# AD_0.net
KiCad netlist of a schematic drawn in Altium Designer
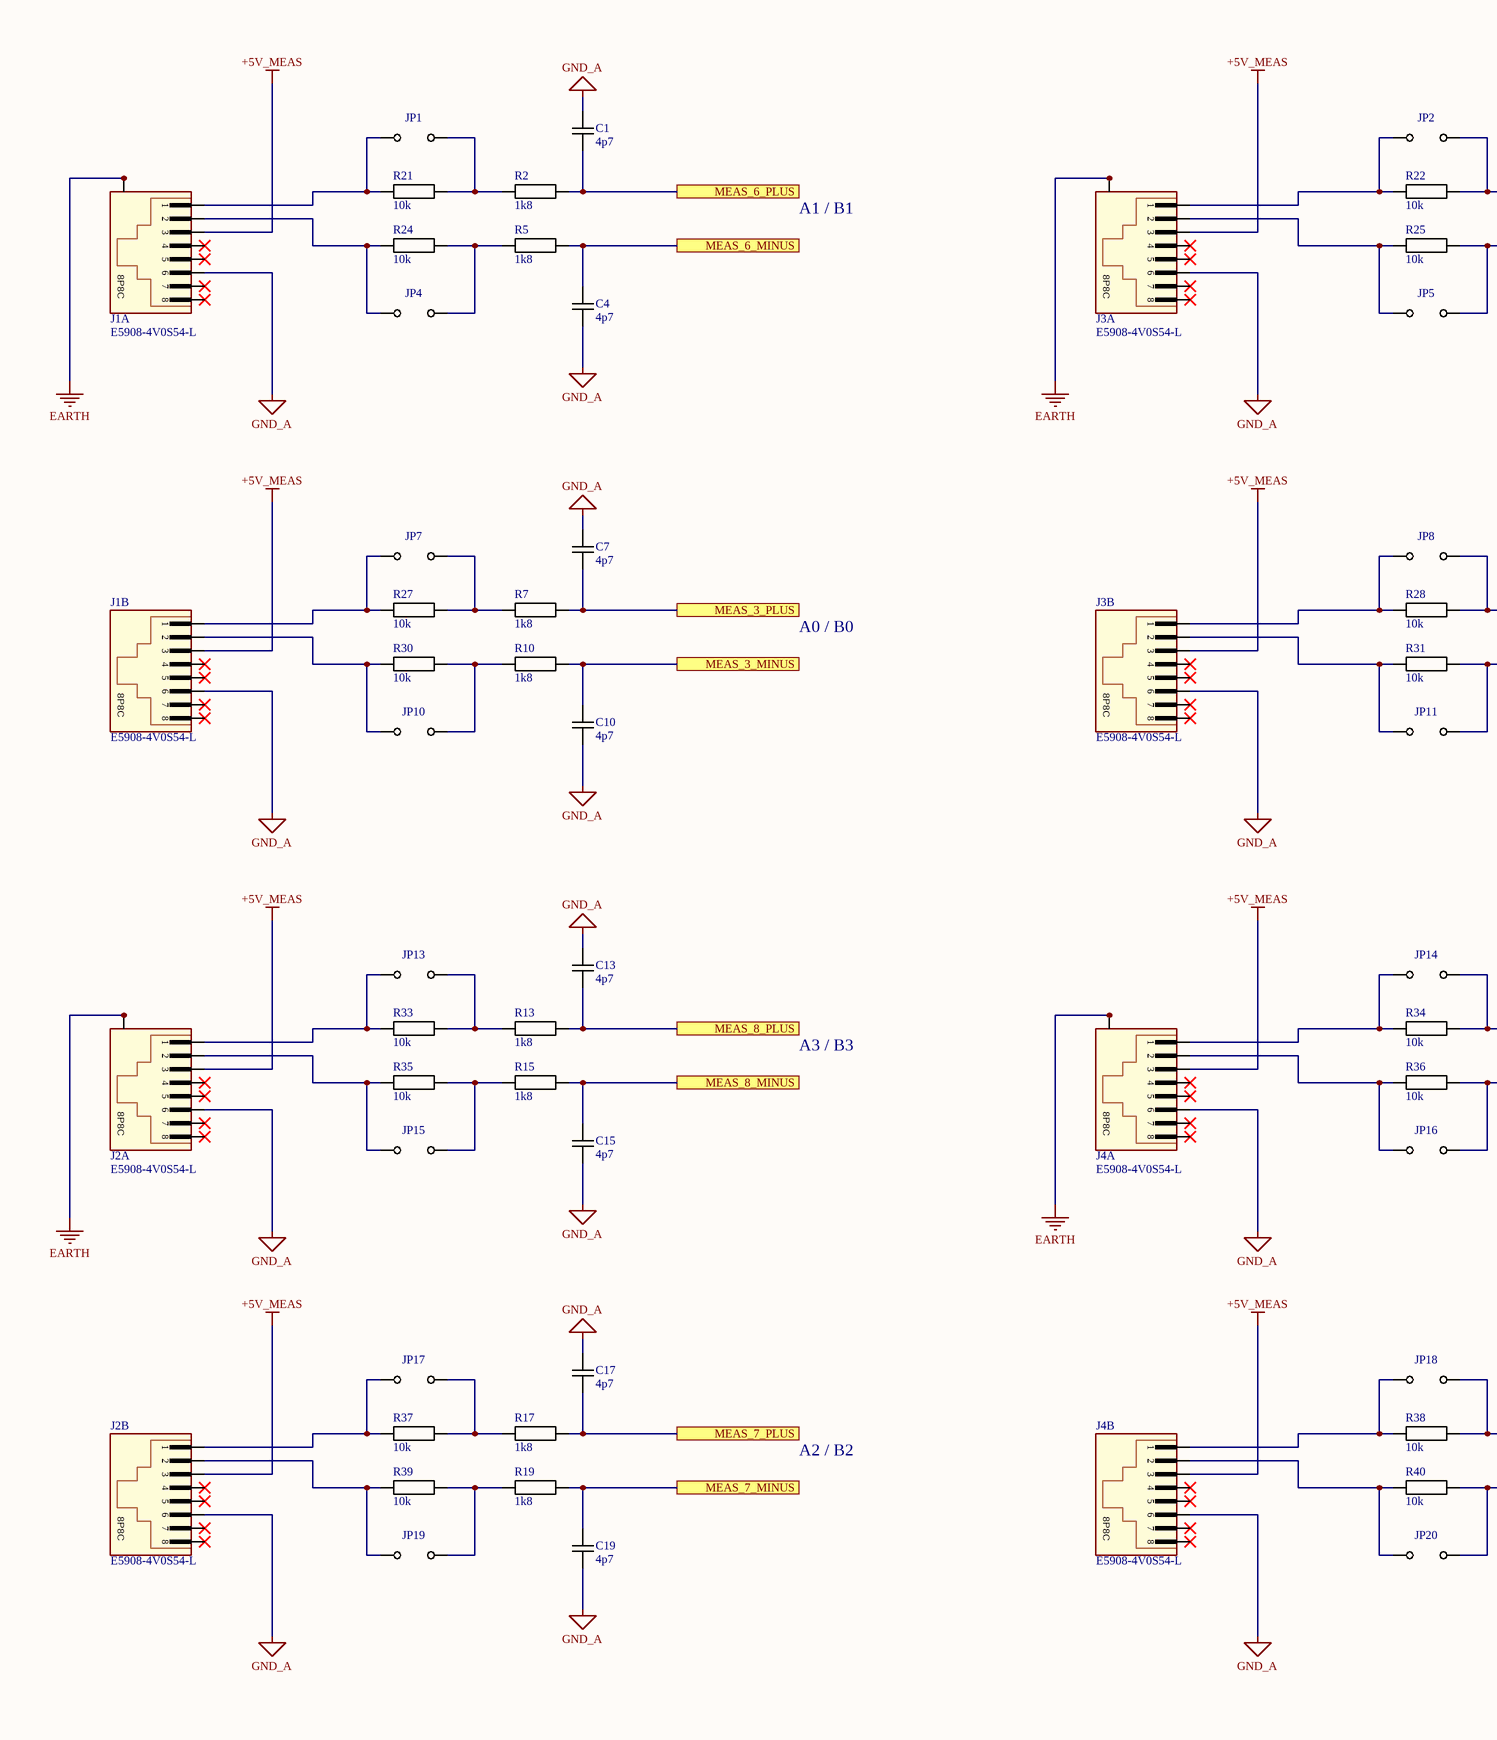
[diagram p0: AD_0.SchDoc, left]
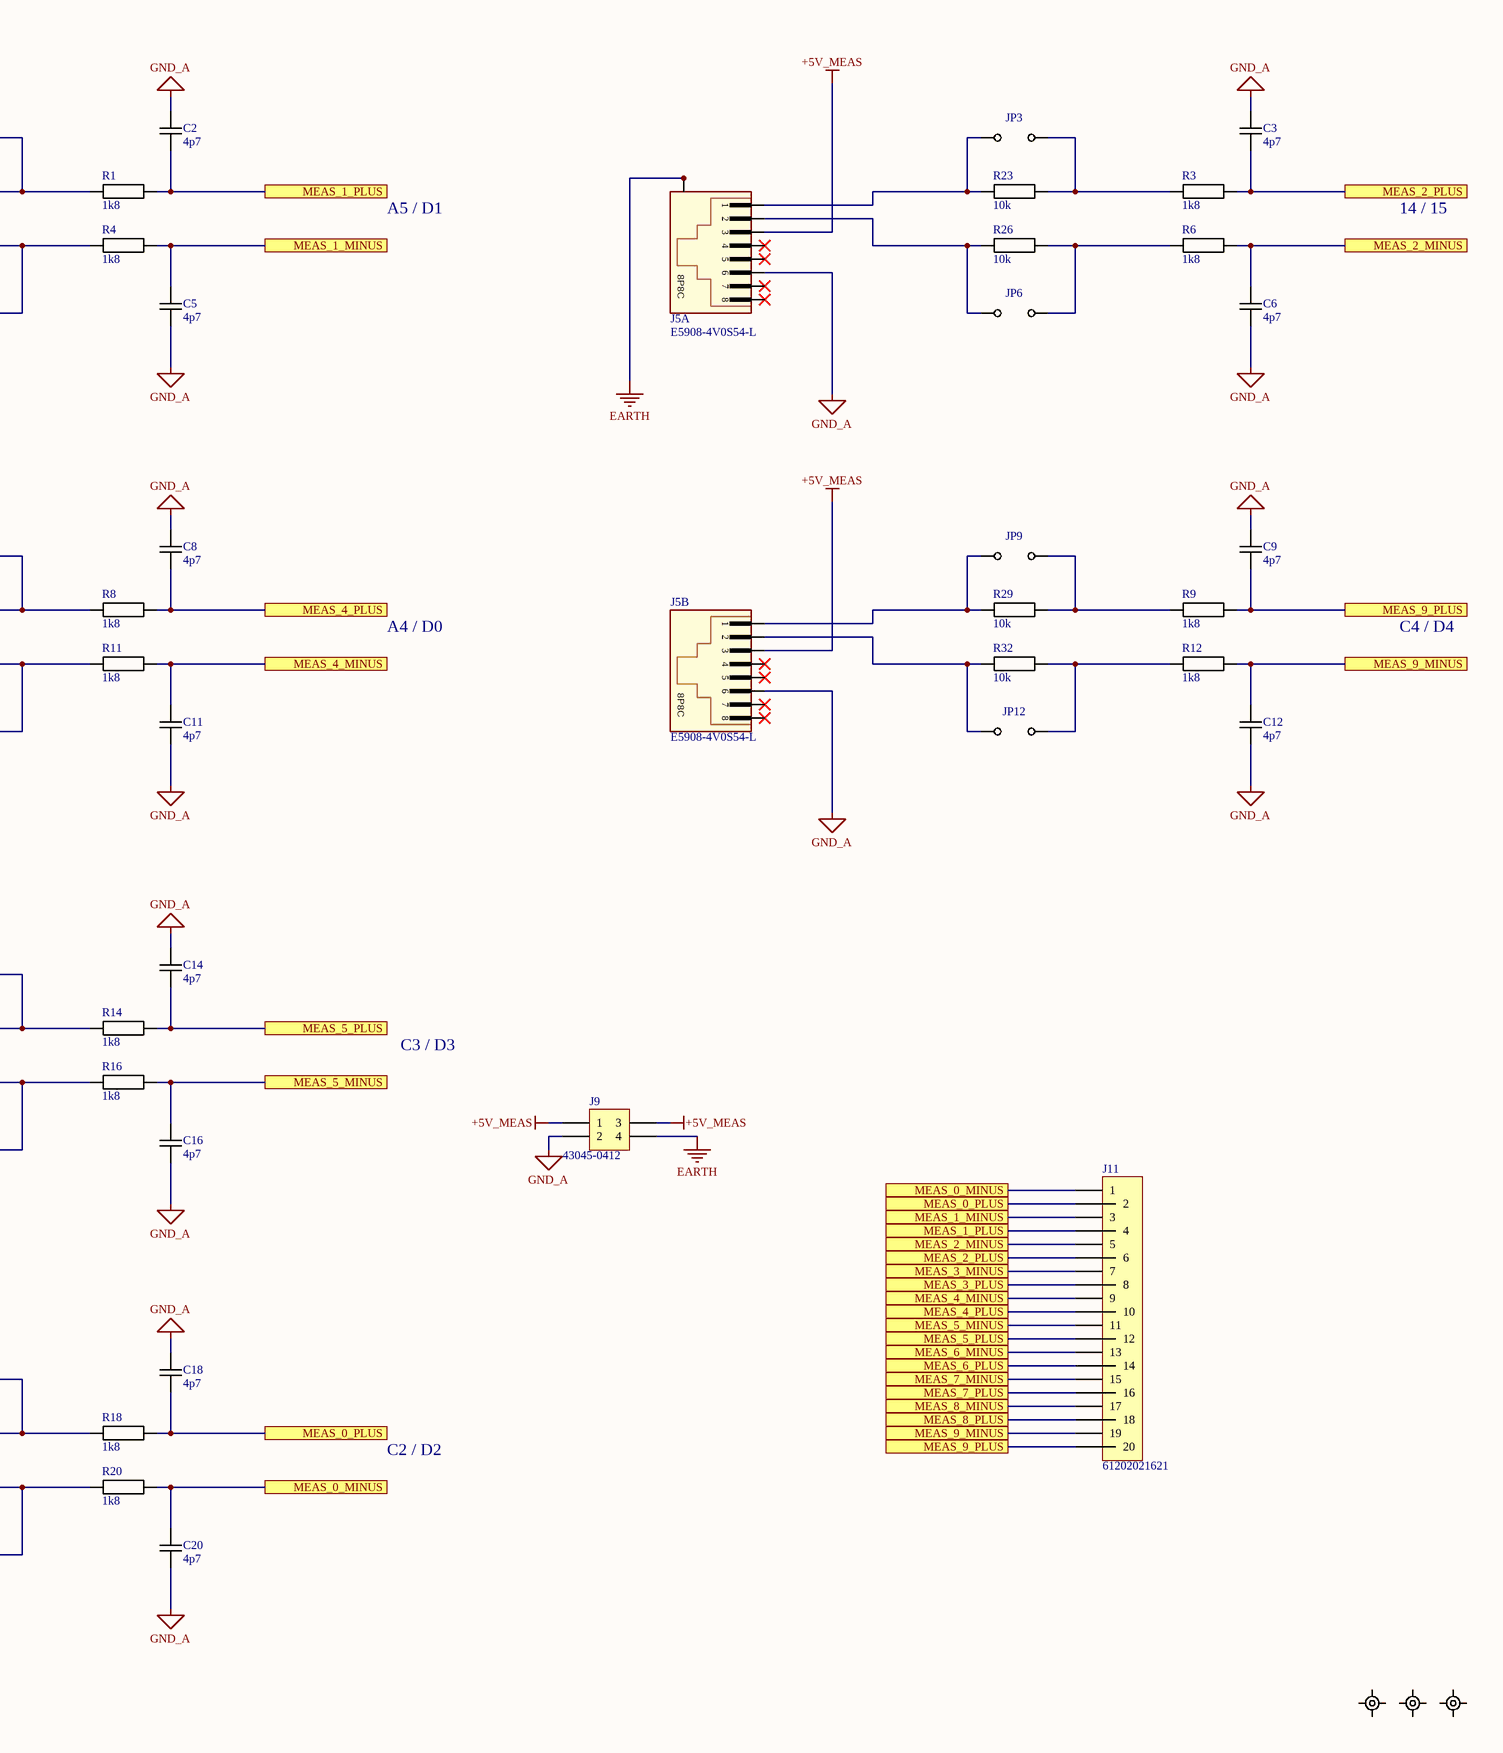
[diagram p1: AD_0.SchDoc, right]

(export (version "E")
  (design (tool "Eeschema 10.0.6"))
  (components
    (comp (ref "C1")
      (value "4p7")
      (footprint "CAPACITOR 2012 REFLOW")
      (description "Capacitor X7R 50V 2012(0805)")
      (libsource (lib "Capacitor") (part "Capacitor"))
    )
    (comp (ref "C2")
      (value "4p7")
      (footprint "CAPACITOR 2012 REFLOW")
      (description "Capacitor X7R 50V 2012(0805)")
      (libsource (lib "Capacitor") (part "Capacitor"))
    )
    (comp (ref "C3")
      (value "4p7")
      (footprint "CAPACITOR 2012 REFLOW")
      (description "Capacitor X7R 50V 2012(0805)")
      (libsource (lib "Capacitor") (part "Capacitor"))
    )
    (comp (ref "C4")
      (value "4p7")
      (footprint "CAPACITOR 2012 REFLOW")
      (description "Capacitor X7R 50V 2012(0805)")
      (libsource (lib "Capacitor") (part "Capacitor"))
    )
    (comp (ref "C5")
      (value "4p7")
      (footprint "CAPACITOR 2012 REFLOW")
      (description "Capacitor X7R 50V 2012(0805)")
      (libsource (lib "Capacitor") (part "Capacitor"))
    )
    (comp (ref "C6")
      (value "4p7")
      (footprint "CAPACITOR 2012 REFLOW")
      (description "Capacitor X7R 50V 2012(0805)")
      (libsource (lib "Capacitor") (part "Capacitor"))
    )
    (comp (ref "C7")
      (value "4p7")
      (footprint "CAPACITOR 2012 REFLOW")
      (description "Capacitor X7R 50V 2012(0805)")
      (libsource (lib "Capacitor") (part "Capacitor"))
    )
    (comp (ref "C8")
      (value "4p7")
      (footprint "CAPACITOR 2012 REFLOW")
      (description "Capacitor X7R 50V 2012(0805)")
      (libsource (lib "Capacitor") (part "Capacitor"))
    )
    (comp (ref "C9")
      (value "4p7")
      (footprint "CAPACITOR 2012 REFLOW")
      (description "Capacitor X7R 50V 2012(0805)")
      (libsource (lib "Capacitor") (part "Capacitor"))
    )
    (comp (ref "C10")
      (value "4p7")
      (footprint "CAPACITOR 2012 REFLOW")
      (description "Capacitor X7R 50V 2012(0805)")
      (libsource (lib "Capacitor") (part "Capacitor"))
    )
    (comp (ref "C11")
      (value "4p7")
      (footprint "CAPACITOR 2012 REFLOW")
      (description "Capacitor X7R 50V 2012(0805)")
      (libsource (lib "Capacitor") (part "Capacitor"))
    )
    (comp (ref "C12")
      (value "4p7")
      (footprint "CAPACITOR 2012 REFLOW")
      (description "Capacitor X7R 50V 2012(0805)")
      (libsource (lib "Capacitor") (part "Capacitor"))
    )
    (comp (ref "C13")
      (value "4p7")
      (footprint "CAPACITOR 2012 REFLOW")
      (description "Capacitor X7R 50V 2012(0805)")
      (libsource (lib "Capacitor") (part "Capacitor"))
    )
    (comp (ref "C14")
      (value "4p7")
      (footprint "CAPACITOR 2012 REFLOW")
      (description "Capacitor X7R 50V 2012(0805)")
      (libsource (lib "Capacitor") (part "Capacitor"))
    )
    (comp (ref "C15")
      (value "4p7")
      (footprint "CAPACITOR 2012 REFLOW")
      (description "Capacitor X7R 50V 2012(0805)")
      (libsource (lib "Capacitor") (part "Capacitor"))
    )
    (comp (ref "C16")
      (value "4p7")
      (footprint "CAPACITOR 2012 REFLOW")
      (description "Capacitor X7R 50V 2012(0805)")
      (libsource (lib "Capacitor") (part "Capacitor"))
    )
    (comp (ref "C17")
      (value "4p7")
      (footprint "CAPACITOR 2012 REFLOW")
      (description "Capacitor X7R 50V 2012(0805)")
      (libsource (lib "Capacitor") (part "Capacitor"))
    )
    (comp (ref "C18")
      (value "4p7")
      (footprint "CAPACITOR 2012 REFLOW")
      (description "Capacitor X7R 50V 2012(0805)")
      (libsource (lib "Capacitor") (part "Capacitor"))
    )
    (comp (ref "C19")
      (value "4p7")
      (footprint "CAPACITOR 2012 REFLOW")
      (description "Capacitor X7R 50V 2012(0805)")
      (libsource (lib "Capacitor") (part "Capacitor"))
    )
    (comp (ref "C20")
      (value "4p7")
      (footprint "CAPACITOR 2012 REFLOW")
      (description "Capacitor X7R 50V 2012(0805)")
      (libsource (lib "Capacitor") (part "Capacitor"))
    )
    (comp (ref "J1")
      (value "E5908-4V0S54-L")
      (footprint "RJ45 8P8C PULSE E5908-4V0S54-L")
      (description "RJ45 2X1 8P8C Ethernet Connectors CONN 30u Au THT")
      (fields (field (name "MANUFACTURER") "Pulse Electronics"))
      (libsource (lib "Connector") (part "RJ45 8P8C PULSE E5908-4V0S54-L"))
    )
    (comp (ref "J2")
      (value "E5908-4V0S54-L")
      (footprint "RJ45 8P8C PULSE E5908-4V0S54-L")
      (description "RJ45 2X1 8P8C Ethernet Connectors CONN 30u Au THT")
      (fields (field (name "MANUFACTURER") "Pulse Electronics"))
      (libsource (lib "Connector") (part "RJ45 8P8C PULSE E5908-4V0S54-L"))
    )
    (comp (ref "J3")
      (value "E5908-4V0S54-L")
      (footprint "RJ45 8P8C PULSE E5908-4V0S54-L")
      (description "RJ45 2X1 8P8C Ethernet Connectors CONN 30u Au THT")
      (fields (field (name "MANUFACTURER") "Pulse Electronics"))
      (libsource (lib "Connector") (part "RJ45 8P8C PULSE E5908-4V0S54-L"))
    )
    (comp (ref "J4")
      (value "E5908-4V0S54-L")
      (footprint "RJ45 8P8C PULSE E5908-4V0S54-L")
      (description "RJ45 2X1 8P8C Ethernet Connectors CONN 30u Au THT")
      (fields (field (name "MANUFACTURER") "Pulse Electronics"))
      (libsource (lib "Connector") (part "RJ45 8P8C PULSE E5908-4V0S54-L"))
    )
    (comp (ref "J5")
      (value "E5908-4V0S54-L")
      (footprint "RJ45 8P8C PULSE E5908-4V0S54-L")
      (description "RJ45 2X1 8P8C Ethernet Connectors CONN 30u Au THT")
      (fields (field (name "MANUFACTURER") "Pulse Electronics"))
      (libsource (lib "Connector") (part "RJ45 8P8C PULSE E5908-4V0S54-L"))
    )
    (comp (ref "J9")
      (value "43045-0412")
      (footprint "MOLEX 43045-0412")
      (description "Micro-Fit 3.0 Vertical Header, 3.00mm Pitch, Dual Row, 4 Circuits")
      (fields (field (name "MANUFACTURER") "Molex"))
      (libsource (lib "Connector") (part "MOLEX 43045-0412"))
    )
    (comp (ref "J11")
      (value "61202021621")
      (footprint "FlatCable2x10 2.54MM Straight TH")
      (description "FlatCable2x10 2.54mm Straight TH")
      (fields (field (name "MANUFACTURER") "Wurth Elektronik"))
      (libsource (lib "Connector") (part "FlatCable2x10"))
    )
    (comp (ref "JP1")
      (value "890-18-036-10-803")
      (footprint "JUMPER2 TH")
      (description "JUMPER 2 POS")
      (fields (field (name "MANUFACTURER") "PRECI-DIP"))
      (libsource (lib "Jumper") (part "JUMPER 2 POS"))
    )
    (comp (ref "JP2")
      (value "890-18-036-10-803")
      (footprint "JUMPER2 TH")
      (description "JUMPER 2 POS")
      (fields (field (name "MANUFACTURER") "PRECI-DIP"))
      (libsource (lib "Jumper") (part "JUMPER 2 POS"))
    )
    (comp (ref "JP3")
      (value "890-18-036-10-803")
      (footprint "JUMPER2 TH")
      (description "JUMPER 2 POS")
      (fields (field (name "MANUFACTURER") "PRECI-DIP"))
      (libsource (lib "Jumper") (part "JUMPER 2 POS"))
    )
    (comp (ref "JP4")
      (value "890-18-036-10-803")
      (footprint "JUMPER2 TH")
      (description "JUMPER 2 POS")
      (fields (field (name "MANUFACTURER") "PRECI-DIP"))
      (libsource (lib "Jumper") (part "JUMPER 2 POS"))
    )
    (comp (ref "JP5")
      (value "890-18-036-10-803")
      (footprint "JUMPER2 TH")
      (description "JUMPER 2 POS")
      (fields (field (name "MANUFACTURER") "PRECI-DIP"))
      (libsource (lib "Jumper") (part "JUMPER 2 POS"))
    )
    (comp (ref "JP6")
      (value "890-18-036-10-803")
      (footprint "JUMPER2 TH")
      (description "JUMPER 2 POS")
      (fields (field (name "MANUFACTURER") "PRECI-DIP"))
      (libsource (lib "Jumper") (part "JUMPER 2 POS"))
    )
    (comp (ref "JP7")
      (value "890-18-036-10-803")
      (footprint "JUMPER2 TH")
      (description "JUMPER 2 POS")
      (fields (field (name "MANUFACTURER") "PRECI-DIP"))
      (libsource (lib "Jumper") (part "JUMPER 2 POS"))
    )
    (comp (ref "JP8")
      (value "890-18-036-10-803")
      (footprint "JUMPER2 TH")
      (description "JUMPER 2 POS")
      (fields (field (name "MANUFACTURER") "PRECI-DIP"))
      (libsource (lib "Jumper") (part "JUMPER 2 POS"))
    )
    (comp (ref "JP9")
      (value "890-18-036-10-803")
      (footprint "JUMPER2 TH")
      (description "JUMPER 2 POS")
      (fields (field (name "MANUFACTURER") "PRECI-DIP"))
      (libsource (lib "Jumper") (part "JUMPER 2 POS"))
    )
    (comp (ref "JP10")
      (value "890-18-036-10-803")
      (footprint "JUMPER2 TH")
      (description "JUMPER 2 POS")
      (fields (field (name "MANUFACTURER") "PRECI-DIP"))
      (libsource (lib "Jumper") (part "JUMPER 2 POS"))
    )
    (comp (ref "JP11")
      (value "890-18-036-10-803")
      (footprint "JUMPER2 TH")
      (description "JUMPER 2 POS")
      (fields (field (name "MANUFACTURER") "PRECI-DIP"))
      (libsource (lib "Jumper") (part "JUMPER 2 POS"))
    )
    (comp (ref "JP12")
      (value "890-18-036-10-803")
      (footprint "JUMPER2 TH")
      (description "JUMPER 2 POS")
      (fields (field (name "MANUFACTURER") "PRECI-DIP"))
      (libsource (lib "Jumper") (part "JUMPER 2 POS"))
    )
    (comp (ref "JP13")
      (value "890-18-036-10-803")
      (footprint "JUMPER2 TH")
      (description "JUMPER 2 POS")
      (fields (field (name "MANUFACTURER") "PRECI-DIP"))
      (libsource (lib "Jumper") (part "JUMPER 2 POS"))
    )
    (comp (ref "JP14")
      (value "890-18-036-10-803")
      (footprint "JUMPER2 TH")
      (description "JUMPER 2 POS")
      (fields (field (name "MANUFACTURER") "PRECI-DIP"))
      (libsource (lib "Jumper") (part "JUMPER 2 POS"))
    )
    (comp (ref "JP15")
      (value "890-18-036-10-803")
      (footprint "JUMPER2 TH")
      (description "JUMPER 2 POS")
      (fields (field (name "MANUFACTURER") "PRECI-DIP"))
      (libsource (lib "Jumper") (part "JUMPER 2 POS"))
    )
    (comp (ref "JP16")
      (value "890-18-036-10-803")
      (footprint "JUMPER2 TH")
      (description "JUMPER 2 POS")
      (fields (field (name "MANUFACTURER") "PRECI-DIP"))
      (libsource (lib "Jumper") (part "JUMPER 2 POS"))
    )
    (comp (ref "JP17")
      (value "890-18-036-10-803")
      (footprint "JUMPER2 TH")
      (description "JUMPER 2 POS")
      (fields (field (name "MANUFACTURER") "PRECI-DIP"))
      (libsource (lib "Jumper") (part "JUMPER 2 POS"))
    )
    (comp (ref "JP18")
      (value "890-18-036-10-803")
      (footprint "JUMPER2 TH")
      (description "JUMPER 2 POS")
      (fields (field (name "MANUFACTURER") "PRECI-DIP"))
      (libsource (lib "Jumper") (part "JUMPER 2 POS"))
    )
    (comp (ref "JP19")
      (value "890-18-036-10-803")
      (footprint "JUMPER2 TH")
      (description "JUMPER 2 POS")
      (fields (field (name "MANUFACTURER") "PRECI-DIP"))
      (libsource (lib "Jumper") (part "JUMPER 2 POS"))
    )
    (comp (ref "JP20")
      (value "890-18-036-10-803")
      (footprint "JUMPER2 TH")
      (description "JUMPER 2 POS")
      (fields (field (name "MANUFACTURER") "PRECI-DIP"))
      (libsource (lib "Jumper") (part "JUMPER 2 POS"))
    )
    (comp (ref "R1")
      (value "1k8")
      (footprint "RESISTOR 2012 REFLOW")
      (description "Resistor 1% 50V 125mW 2012(0805)")
      (libsource (lib "Resistor") (part "Resistor"))
    )
    (comp (ref "R2")
      (value "1k8")
      (footprint "RESISTOR 2012 REFLOW")
      (description "Resistor 1% 50V 125mW 2012(0805)")
      (libsource (lib "Resistor") (part "Resistor"))
    )
    (comp (ref "R3")
      (value "1k8")
      (footprint "RESISTOR 2012 REFLOW")
      (description "Resistor 1% 50V 125mW 2012(0805)")
      (libsource (lib "Resistor") (part "Resistor"))
    )
    (comp (ref "R4")
      (value "1k8")
      (footprint "RESISTOR 2012 REFLOW")
      (description "Resistor 1% 50V 125mW 2012(0805)")
      (libsource (lib "Resistor") (part "Resistor"))
    )
    (comp (ref "R5")
      (value "1k8")
      (footprint "RESISTOR 2012 REFLOW")
      (description "Resistor 1% 50V 125mW 2012(0805)")
      (libsource (lib "Resistor") (part "Resistor"))
    )
    (comp (ref "R6")
      (value "1k8")
      (footprint "RESISTOR 2012 REFLOW")
      (description "Resistor 1% 50V 125mW 2012(0805)")
      (libsource (lib "Resistor") (part "Resistor"))
    )
    (comp (ref "R7")
      (value "1k8")
      (footprint "RESISTOR 2012 REFLOW")
      (description "Resistor 1% 50V 125mW 2012(0805)")
      (libsource (lib "Resistor") (part "Resistor"))
    )
    (comp (ref "R8")
      (value "1k8")
      (footprint "RESISTOR 2012 REFLOW")
      (description "Resistor 1% 50V 125mW 2012(0805)")
      (libsource (lib "Resistor") (part "Resistor"))
    )
    (comp (ref "R9")
      (value "1k8")
      (footprint "RESISTOR 2012 REFLOW")
      (description "Resistor 1% 50V 125mW 2012(0805)")
      (libsource (lib "Resistor") (part "Resistor"))
    )
    (comp (ref "R10")
      (value "1k8")
      (footprint "RESISTOR 2012 REFLOW")
      (description "Resistor 1% 50V 125mW 2012(0805)")
      (libsource (lib "Resistor") (part "Resistor"))
    )
    (comp (ref "R11")
      (value "1k8")
      (footprint "RESISTOR 2012 REFLOW")
      (description "Resistor 1% 50V 125mW 2012(0805)")
      (libsource (lib "Resistor") (part "Resistor"))
    )
    (comp (ref "R12")
      (value "1k8")
      (footprint "RESISTOR 2012 REFLOW")
      (description "Resistor 1% 50V 125mW 2012(0805)")
      (libsource (lib "Resistor") (part "Resistor"))
    )
    (comp (ref "R13")
      (value "1k8")
      (footprint "RESISTOR 2012 REFLOW")
      (description "Resistor 1% 50V 125mW 2012(0805)")
      (libsource (lib "Resistor") (part "Resistor"))
    )
    (comp (ref "R14")
      (value "1k8")
      (footprint "RESISTOR 2012 REFLOW")
      (description "Resistor 1% 50V 125mW 2012(0805)")
      (libsource (lib "Resistor") (part "Resistor"))
    )
    (comp (ref "R15")
      (value "1k8")
      (footprint "RESISTOR 2012 REFLOW")
      (description "Resistor 1% 50V 125mW 2012(0805)")
      (libsource (lib "Resistor") (part "Resistor"))
    )
    (comp (ref "R16")
      (value "1k8")
      (footprint "RESISTOR 2012 REFLOW")
      (description "Resistor 1% 50V 125mW 2012(0805)")
      (libsource (lib "Resistor") (part "Resistor"))
    )
    (comp (ref "R17")
      (value "1k8")
      (footprint "RESISTOR 2012 REFLOW")
      (description "Resistor 1% 50V 125mW 2012(0805)")
      (libsource (lib "Resistor") (part "Resistor"))
    )
    (comp (ref "R18")
      (value "1k8")
      (footprint "RESISTOR 2012 REFLOW")
      (description "Resistor 1% 50V 125mW 2012(0805)")
      (libsource (lib "Resistor") (part "Resistor"))
    )
    (comp (ref "R19")
      (value "1k8")
      (footprint "RESISTOR 2012 REFLOW")
      (description "Resistor 1% 50V 125mW 2012(0805)")
      (libsource (lib "Resistor") (part "Resistor"))
    )
    (comp (ref "R20")
      (value "1k8")
      (footprint "RESISTOR 2012 REFLOW")
      (description "Resistor 1% 50V 125mW 2012(0805)")
      (libsource (lib "Resistor") (part "Resistor"))
    )
    (comp (ref "R21")
      (value "10k")
      (footprint "RESISTOR 2012 REFLOW")
      (description "Resistor 1% 50V 125mW 2012(0805)")
      (libsource (lib "Resistor") (part "Resistor"))
    )
    (comp (ref "R22")
      (value "10k")
      (footprint "RESISTOR 2012 REFLOW")
      (description "Resistor 1% 50V 125mW 2012(0805)")
      (libsource (lib "Resistor") (part "Resistor"))
    )
    (comp (ref "R23")
      (value "10k")
      (footprint "RESISTOR 2012 REFLOW")
      (description "Resistor 1% 50V 125mW 2012(0805)")
      (libsource (lib "Resistor") (part "Resistor"))
    )
    (comp (ref "R24")
      (value "10k")
      (footprint "RESISTOR 2012 REFLOW")
      (description "Resistor 1% 50V 125mW 2012(0805)")
      (libsource (lib "Resistor") (part "Resistor"))
    )
    (comp (ref "R25")
      (value "10k")
      (footprint "RESISTOR 2012 REFLOW")
      (description "Resistor 1% 50V 125mW 2012(0805)")
      (libsource (lib "Resistor") (part "Resistor"))
    )
    (comp (ref "R26")
      (value "10k")
      (footprint "RESISTOR 2012 REFLOW")
      (description "Resistor 1% 50V 125mW 2012(0805)")
      (libsource (lib "Resistor") (part "Resistor"))
    )
    (comp (ref "R27")
      (value "10k")
      (footprint "RESISTOR 2012 REFLOW")
      (description "Resistor 1% 50V 125mW 2012(0805)")
      (libsource (lib "Resistor") (part "Resistor"))
    )
    (comp (ref "R28")
      (value "10k")
      (footprint "RESISTOR 2012 REFLOW")
      (description "Resistor 1% 50V 125mW 2012(0805)")
      (libsource (lib "Resistor") (part "Resistor"))
    )
    (comp (ref "R29")
      (value "10k")
      (footprint "RESISTOR 2012 REFLOW")
      (description "Resistor 1% 50V 125mW 2012(0805)")
      (libsource (lib "Resistor") (part "Resistor"))
    )
    (comp (ref "R30")
      (value "10k")
      (footprint "RESISTOR 2012 REFLOW")
      (description "Resistor 1% 50V 125mW 2012(0805)")
      (libsource (lib "Resistor") (part "Resistor"))
    )
    (comp (ref "R31")
      (value "10k")
      (footprint "RESISTOR 2012 REFLOW")
      (description "Resistor 1% 50V 125mW 2012(0805)")
      (libsource (lib "Resistor") (part "Resistor"))
    )
    (comp (ref "R32")
      (value "10k")
      (footprint "RESISTOR 2012 REFLOW")
      (description "Resistor 1% 50V 125mW 2012(0805)")
      (libsource (lib "Resistor") (part "Resistor"))
    )
    (comp (ref "R33")
      (value "10k")
      (footprint "RESISTOR 2012 REFLOW")
      (description "Resistor 1% 50V 125mW 2012(0805)")
      (libsource (lib "Resistor") (part "Resistor"))
    )
    (comp (ref "R34")
      (value "10k")
      (footprint "RESISTOR 2012 REFLOW")
      (description "Resistor 1% 50V 125mW 2012(0805)")
      (libsource (lib "Resistor") (part "Resistor"))
    )
    (comp (ref "R35")
      (value "10k")
      (footprint "RESISTOR 2012 REFLOW")
      (description "Resistor 1% 50V 125mW 2012(0805)")
      (libsource (lib "Resistor") (part "Resistor"))
    )
    (comp (ref "R36")
      (value "10k")
      (footprint "RESISTOR 2012 REFLOW")
      (description "Resistor 1% 50V 125mW 2012(0805)")
      (libsource (lib "Resistor") (part "Resistor"))
    )
    (comp (ref "R37")
      (value "10k")
      (footprint "RESISTOR 2012 REFLOW")
      (description "Resistor 1% 50V 125mW 2012(0805)")
      (libsource (lib "Resistor") (part "Resistor"))
    )
    (comp (ref "R38")
      (value "10k")
      (footprint "RESISTOR 2012 REFLOW")
      (description "Resistor 1% 50V 125mW 2012(0805)")
      (libsource (lib "Resistor") (part "Resistor"))
    )
    (comp (ref "R39")
      (value "10k")
      (footprint "RESISTOR 2012 REFLOW")
      (description "Resistor 1% 50V 125mW 2012(0805)")
      (libsource (lib "Resistor") (part "Resistor"))
    )
    (comp (ref "R40")
      (value "10k")
      (footprint "RESISTOR 2012 REFLOW")
      (description "Resistor 1% 50V 125mW 2012(0805)")
      (libsource (lib "Resistor") (part "Resistor"))
    )
    (comp (ref "Z1")
      (value "1 - 3")
      (footprint "FIDUCIAL")
      (description "FIDUCIAL Din 1mm Dout 3mm")
      (libsource (lib "Mechanic") (part "FIDUCIAL"))
    )
    (comp (ref "Z2")
      (value "1 - 3")
      (footprint "FIDUCIAL")
      (description "FIDUCIAL Din 1mm Dout 3mm")
      (libsource (lib "Mechanic") (part "FIDUCIAL"))
    )
    (comp (ref "Z3")
      (value "1 - 3")
      (footprint "FIDUCIAL")
      (description "FIDUCIAL Din 1mm Dout 3mm")
      (libsource (lib "Mechanic") (part "FIDUCIAL"))
    )
  )
  (nets
    (net (code "1") (name "+5V_MEAS") (class "Default")
      (node (ref "J1") (pin "3A") (pinfunction "3A_3A") (pintype "passive"))
      (node (ref "J1") (pin "3B") (pinfunction "3B_3B") (pintype "passive"))
      (node (ref "J2") (pin "3A") (pinfunction "3A_3A") (pintype "passive"))
      (node (ref "J2") (pin "3B") (pinfunction "3B_3B") (pintype "passive"))
      (node (ref "J3") (pin "3A") (pinfunction "3A_3A") (pintype "passive"))
      (node (ref "J3") (pin "3B") (pinfunction "3B_3B") (pintype "passive"))
      (node (ref "J4") (pin "3A") (pinfunction "3A_3A") (pintype "passive"))
      (node (ref "J4") (pin "3B") (pinfunction "3B_3B") (pintype "passive"))
      (node (ref "J5") (pin "3A") (pinfunction "3A_3A") (pintype "passive"))
      (node (ref "J5") (pin "3B") (pinfunction "3B_3B") (pintype "passive"))
      (node (ref "J9") (pin "1") (pinfunction "1_1") (pintype "passive"))
      (node (ref "J9") (pin "3") (pinfunction "3_3") (pintype "passive"))
    )
    (net (code "2") (name "/MEAS_0_MINUS") (class "Default")
      (node (ref "C20") (pin "2") (pinfunction "2_2") (pintype "passive"))
      (node (ref "J11") (pin "1") (pinfunction "1_1") (pintype "passive"))
      (node (ref "R20") (pin "2") (pinfunction "2_2") (pintype "passive"))
    )
    (net (code "3") (name "/MEAS_0_PLUS") (class "Default")
      (node (ref "C18") (pin "1") (pinfunction "1_1") (pintype "passive"))
      (node (ref "J11") (pin "2") (pinfunction "2_2") (pintype "passive"))
      (node (ref "R18") (pin "2") (pinfunction "2_2") (pintype "passive"))
    )
    (net (code "4") (name "/MEAS_1_MINUS") (class "Default")
      (node (ref "C5") (pin "2") (pinfunction "2_2") (pintype "passive"))
      (node (ref "J11") (pin "3") (pinfunction "3_3") (pintype "passive"))
      (node (ref "R4") (pin "2") (pinfunction "2_2") (pintype "passive"))
    )
    (net (code "5") (name "/MEAS_1_PLUS") (class "Default")
      (node (ref "C2") (pin "1") (pinfunction "1_1") (pintype "passive"))
      (node (ref "J11") (pin "4") (pinfunction "4_4") (pintype "passive"))
      (node (ref "R1") (pin "2") (pinfunction "2_2") (pintype "passive"))
    )
    (net (code "6") (name "/MEAS_2_MINUS") (class "Default")
      (node (ref "C6") (pin "2") (pinfunction "2_2") (pintype "passive"))
      (node (ref "J11") (pin "5") (pinfunction "5_5") (pintype "passive"))
      (node (ref "R6") (pin "2") (pinfunction "2_2") (pintype "passive"))
    )
    (net (code "7") (name "/MEAS_2_PLUS") (class "Default")
      (node (ref "C3") (pin "1") (pinfunction "1_1") (pintype "passive"))
      (node (ref "J11") (pin "6") (pinfunction "6_6") (pintype "passive"))
      (node (ref "R3") (pin "2") (pinfunction "2_2") (pintype "passive"))
    )
    (net (code "8") (name "/MEAS_3_MINUS") (class "Default")
      (node (ref "C10") (pin "2") (pinfunction "2_2") (pintype "passive"))
      (node (ref "J11") (pin "7") (pinfunction "7_7") (pintype "passive"))
      (node (ref "R10") (pin "2") (pinfunction "2_2") (pintype "passive"))
    )
    (net (code "9") (name "/MEAS_3_PLUS") (class "Default")
      (node (ref "C7") (pin "1") (pinfunction "1_1") (pintype "passive"))
      (node (ref "J11") (pin "8") (pinfunction "8_8") (pintype "passive"))
      (node (ref "R7") (pin "2") (pinfunction "2_2") (pintype "passive"))
    )
    (net (code "10") (name "/MEAS_4_MINUS") (class "Default")
      (node (ref "C11") (pin "2") (pinfunction "2_2") (pintype "passive"))
      (node (ref "J11") (pin "9") (pinfunction "9_9") (pintype "passive"))
      (node (ref "R11") (pin "2") (pinfunction "2_2") (pintype "passive"))
    )
    (net (code "11") (name "/MEAS_4_PLUS") (class "Default")
      (node (ref "C8") (pin "1") (pinfunction "1_1") (pintype "passive"))
      (node (ref "J11") (pin "10") (pinfunction "10_10") (pintype "passive"))
      (node (ref "R8") (pin "2") (pinfunction "2_2") (pintype "passive"))
    )
    (net (code "12") (name "/MEAS_5_MINUS") (class "Default")
      (node (ref "C16") (pin "2") (pinfunction "2_2") (pintype "passive"))
      (node (ref "J11") (pin "11") (pinfunction "11_11") (pintype "passive"))
      (node (ref "R16") (pin "2") (pinfunction "2_2") (pintype "passive"))
    )
    (net (code "13") (name "/MEAS_5_PLUS") (class "Default")
      (node (ref "C14") (pin "1") (pinfunction "1_1") (pintype "passive"))
      (node (ref "J11") (pin "12") (pinfunction "12_12") (pintype "passive"))
      (node (ref "R14") (pin "2") (pinfunction "2_2") (pintype "passive"))
    )
    (net (code "14") (name "/MEAS_6_MINUS") (class "Default")
      (node (ref "C4") (pin "2") (pinfunction "2_2") (pintype "passive"))
      (node (ref "J11") (pin "13") (pinfunction "13_13") (pintype "passive"))
      (node (ref "R5") (pin "2") (pinfunction "2_2") (pintype "passive"))
    )
    (net (code "15") (name "/MEAS_6_PLUS") (class "Default")
      (node (ref "C1") (pin "1") (pinfunction "1_1") (pintype "passive"))
      (node (ref "J11") (pin "14") (pinfunction "14_14") (pintype "passive"))
      (node (ref "R2") (pin "2") (pinfunction "2_2") (pintype "passive"))
    )
    (net (code "16") (name "/MEAS_7_MINUS") (class "Default")
      (node (ref "C19") (pin "2") (pinfunction "2_2") (pintype "passive"))
      (node (ref "J11") (pin "15") (pinfunction "15_15") (pintype "passive"))
      (node (ref "R19") (pin "2") (pinfunction "2_2") (pintype "passive"))
    )
    (net (code "17") (name "/MEAS_7_PLUS") (class "Default")
      (node (ref "C17") (pin "1") (pinfunction "1_1") (pintype "passive"))
      (node (ref "J11") (pin "16") (pinfunction "16_16") (pintype "passive"))
      (node (ref "R17") (pin "2") (pinfunction "2_2") (pintype "passive"))
    )
    (net (code "18") (name "/MEAS_8_MINUS") (class "Default")
      (node (ref "C15") (pin "2") (pinfunction "2_2") (pintype "passive"))
      (node (ref "J11") (pin "17") (pinfunction "17_17") (pintype "passive"))
      (node (ref "R15") (pin "2") (pinfunction "2_2") (pintype "passive"))
    )
    (net (code "19") (name "/MEAS_8_PLUS") (class "Default")
      (node (ref "C13") (pin "1") (pinfunction "1_1") (pintype "passive"))
      (node (ref "J11") (pin "18") (pinfunction "18_18") (pintype "passive"))
      (node (ref "R13") (pin "2") (pinfunction "2_2") (pintype "passive"))
    )
    (net (code "20") (name "/MEAS_9_MINUS") (class "Default")
      (node (ref "C12") (pin "2") (pinfunction "2_2") (pintype "passive"))
      (node (ref "J11") (pin "19") (pinfunction "19_19") (pintype "passive"))
      (node (ref "R12") (pin "2") (pinfunction "2_2") (pintype "passive"))
    )
    (net (code "21") (name "/MEAS_9_PLUS") (class "Default")
      (node (ref "C9") (pin "1") (pinfunction "1_1") (pintype "passive"))
      (node (ref "J11") (pin "20") (pinfunction "20_20") (pintype "passive"))
      (node (ref "R9") (pin "2") (pinfunction "2_2") (pintype "passive"))
    )
    (net (code "22") (name "EARTH") (class "Default")
      (node (ref "J1") (pin "10") (pinfunction "10_10") (pintype "passive"))
      (node (ref "J1") (pin "11") (pinfunction "11_11") (pintype "passive"))
      (node (ref "J1") (pin "12") (pinfunction "SHIELD_12") (pintype "passive"))
      (node (ref "J1") (pin "9") (pinfunction "9_9") (pintype "passive"))
      (node (ref "J2") (pin "10") (pinfunction "10_10") (pintype "passive"))
      (node (ref "J2") (pin "11") (pinfunction "11_11") (pintype "passive"))
      (node (ref "J2") (pin "12") (pinfunction "SHIELD_12") (pintype "passive"))
      (node (ref "J2") (pin "9") (pinfunction "9_9") (pintype "passive"))
      (node (ref "J3") (pin "10") (pinfunction "10_10") (pintype "passive"))
      (node (ref "J3") (pin "11") (pinfunction "11_11") (pintype "passive"))
      (node (ref "J3") (pin "12") (pinfunction "SHIELD_12") (pintype "passive"))
      (node (ref "J3") (pin "9") (pinfunction "9_9") (pintype "passive"))
      (node (ref "J4") (pin "10") (pinfunction "10_10") (pintype "passive"))
      (node (ref "J4") (pin "11") (pinfunction "11_11") (pintype "passive"))
      (node (ref "J4") (pin "12") (pinfunction "SHIELD_12") (pintype "passive"))
      (node (ref "J4") (pin "9") (pinfunction "9_9") (pintype "passive"))
      (node (ref "J5") (pin "10") (pinfunction "10_10") (pintype "passive"))
      (node (ref "J5") (pin "11") (pinfunction "11_11") (pintype "passive"))
      (node (ref "J5") (pin "12") (pinfunction "SHIELD_12") (pintype "passive"))
      (node (ref "J5") (pin "9") (pinfunction "9_9") (pintype "passive"))
      (node (ref "J9") (pin "4") (pinfunction "4_4") (pintype "passive"))
    )
    (net (code "23") (name "GND_A") (class "Default")
      (node (ref "C1") (pin "2") (pinfunction "2_2") (pintype "passive"))
      (node (ref "C10") (pin "1") (pinfunction "1_1") (pintype "passive"))
      (node (ref "C11") (pin "1") (pinfunction "1_1") (pintype "passive"))
      (node (ref "C12") (pin "1") (pinfunction "1_1") (pintype "passive"))
      (node (ref "C13") (pin "2") (pinfunction "2_2") (pintype "passive"))
      (node (ref "C14") (pin "2") (pinfunction "2_2") (pintype "passive"))
      (node (ref "C15") (pin "1") (pinfunction "1_1") (pintype "passive"))
      (node (ref "C16") (pin "1") (pinfunction "1_1") (pintype "passive"))
      (node (ref "C17") (pin "2") (pinfunction "2_2") (pintype "passive"))
      (node (ref "C18") (pin "2") (pinfunction "2_2") (pintype "passive"))
      (node (ref "C19") (pin "1") (pinfunction "1_1") (pintype "passive"))
      (node (ref "C2") (pin "2") (pinfunction "2_2") (pintype "passive"))
      (node (ref "C20") (pin "1") (pinfunction "1_1") (pintype "passive"))
      (node (ref "C3") (pin "2") (pinfunction "2_2") (pintype "passive"))
      (node (ref "C4") (pin "1") (pinfunction "1_1") (pintype "passive"))
      (node (ref "C5") (pin "1") (pinfunction "1_1") (pintype "passive"))
      (node (ref "C6") (pin "1") (pinfunction "1_1") (pintype "passive"))
      (node (ref "C7") (pin "2") (pinfunction "2_2") (pintype "passive"))
      (node (ref "C8") (pin "2") (pinfunction "2_2") (pintype "passive"))
      (node (ref "C9") (pin "2") (pinfunction "2_2") (pintype "passive"))
      (node (ref "J1") (pin "6A") (pinfunction "6A_6A") (pintype "passive"))
      (node (ref "J1") (pin "6B") (pinfunction "6B_6B") (pintype "passive"))
      (node (ref "J2") (pin "6A") (pinfunction "6A_6A") (pintype "passive"))
      (node (ref "J2") (pin "6B") (pinfunction "6B_6B") (pintype "passive"))
      (node (ref "J3") (pin "6A") (pinfunction "6A_6A") (pintype "passive"))
      (node (ref "J3") (pin "6B") (pinfunction "6B_6B") (pintype "passive"))
      (node (ref "J4") (pin "6A") (pinfunction "6A_6A") (pintype "passive"))
      (node (ref "J4") (pin "6B") (pinfunction "6B_6B") (pintype "passive"))
      (node (ref "J5") (pin "6A") (pinfunction "6A_6A") (pintype "passive"))
      (node (ref "J5") (pin "6B") (pinfunction "6B_6B") (pintype "passive"))
      (node (ref "J9") (pin "2") (pinfunction "2_2") (pintype "passive"))
    )
    (net (code "24") (name "Net-(J1-Pad1A)") (class "Default")
      (node (ref "J1") (pin "1A") (pinfunction "1A_1A") (pintype "passive"))
      (node (ref "JP1") (pin "1") (pinfunction "1_1") (pintype "passive"))
      (node (ref "R21") (pin "1") (pinfunction "1_1") (pintype "passive"))
    )
    (net (code "25") (name "Net-(J1-Pad1B)") (class "Default")
      (node (ref "J1") (pin "1B") (pinfunction "1B_1B") (pintype "passive"))
      (node (ref "JP7") (pin "1") (pinfunction "1_1") (pintype "passive"))
      (node (ref "R27") (pin "1") (pinfunction "1_1") (pintype "passive"))
    )
    (net (code "26") (name "Net-(J1-Pad2A)") (class "Default")
      (node (ref "J1") (pin "2A") (pinfunction "2A_2A") (pintype "passive"))
      (node (ref "JP4") (pin "1") (pinfunction "1_1") (pintype "passive"))
      (node (ref "R24") (pin "2") (pinfunction "2_2") (pintype "passive"))
    )
    (net (code "27") (name "Net-(J1-Pad2B)") (class "Default")
      (node (ref "J1") (pin "2B") (pinfunction "2B_2B") (pintype "passive"))
      (node (ref "JP10") (pin "1") (pinfunction "1_1") (pintype "passive"))
      (node (ref "R30") (pin "2") (pinfunction "2_2") (pintype "passive"))
    )
    (net (code "28") (name "Net-(J2-Pad1A)") (class "Default")
      (node (ref "J2") (pin "1A") (pinfunction "1A_1A") (pintype "passive"))
      (node (ref "JP13") (pin "1") (pinfunction "1_1") (pintype "passive"))
      (node (ref "R33") (pin "1") (pinfunction "1_1") (pintype "passive"))
    )
    (net (code "29") (name "Net-(J2-Pad1B)") (class "Default")
      (node (ref "J2") (pin "1B") (pinfunction "1B_1B") (pintype "passive"))
      (node (ref "JP17") (pin "1") (pinfunction "1_1") (pintype "passive"))
      (node (ref "R37") (pin "1") (pinfunction "1_1") (pintype "passive"))
    )
    (net (code "30") (name "Net-(J2-Pad2A)") (class "Default")
      (node (ref "J2") (pin "2A") (pinfunction "2A_2A") (pintype "passive"))
      (node (ref "JP15") (pin "1") (pinfunction "1_1") (pintype "passive"))
      (node (ref "R35") (pin "2") (pinfunction "2_2") (pintype "passive"))
    )
    (net (code "31") (name "Net-(J2-Pad2B)") (class "Default")
      (node (ref "J2") (pin "2B") (pinfunction "2B_2B") (pintype "passive"))
      (node (ref "JP19") (pin "1") (pinfunction "1_1") (pintype "passive"))
      (node (ref "R39") (pin "2") (pinfunction "2_2") (pintype "passive"))
    )
    (net (code "32") (name "Net-(J3-Pad1A)") (class "Default")
      (node (ref "J3") (pin "1A") (pinfunction "1A_1A") (pintype "passive"))
      (node (ref "JP2") (pin "1") (pinfunction "1_1") (pintype "passive"))
      (node (ref "R22") (pin "1") (pinfunction "1_1") (pintype "passive"))
    )
    (net (code "33") (name "Net-(J3-Pad1B)") (class "Default")
      (node (ref "J3") (pin "1B") (pinfunction "1B_1B") (pintype "passive"))
      (node (ref "JP8") (pin "1") (pinfunction "1_1") (pintype "passive"))
      (node (ref "R28") (pin "1") (pinfunction "1_1") (pintype "passive"))
    )
    (net (code "34") (name "Net-(J3-Pad2A)") (class "Default")
      (node (ref "J3") (pin "2A") (pinfunction "2A_2A") (pintype "passive"))
      (node (ref "JP5") (pin "1") (pinfunction "1_1") (pintype "passive"))
      (node (ref "R25") (pin "2") (pinfunction "2_2") (pintype "passive"))
    )
    (net (code "35") (name "Net-(J3-Pad2B)") (class "Default")
      (node (ref "J3") (pin "2B") (pinfunction "2B_2B") (pintype "passive"))
      (node (ref "JP11") (pin "1") (pinfunction "1_1") (pintype "passive"))
      (node (ref "R31") (pin "2") (pinfunction "2_2") (pintype "passive"))
    )
    (net (code "36") (name "Net-(J4-Pad1A)") (class "Default")
      (node (ref "J4") (pin "1A") (pinfunction "1A_1A") (pintype "passive"))
      (node (ref "JP14") (pin "1") (pinfunction "1_1") (pintype "passive"))
      (node (ref "R34") (pin "1") (pinfunction "1_1") (pintype "passive"))
    )
    (net (code "37") (name "Net-(J4-Pad1B)") (class "Default")
      (node (ref "J4") (pin "1B") (pinfunction "1B_1B") (pintype "passive"))
      (node (ref "JP18") (pin "1") (pinfunction "1_1") (pintype "passive"))
      (node (ref "R38") (pin "1") (pinfunction "1_1") (pintype "passive"))
    )
    (net (code "38") (name "Net-(J4-Pad2A)") (class "Default")
      (node (ref "J4") (pin "2A") (pinfunction "2A_2A") (pintype "passive"))
      (node (ref "JP16") (pin "1") (pinfunction "1_1") (pintype "passive"))
      (node (ref "R36") (pin "2") (pinfunction "2_2") (pintype "passive"))
    )
    (net (code "39") (name "Net-(J4-Pad2B)") (class "Default")
      (node (ref "J4") (pin "2B") (pinfunction "2B_2B") (pintype "passive"))
      (node (ref "JP20") (pin "1") (pinfunction "1_1") (pintype "passive"))
      (node (ref "R40") (pin "2") (pinfunction "2_2") (pintype "passive"))
    )
    (net (code "40") (name "Net-(J5-Pad1A)") (class "Default")
      (node (ref "J5") (pin "1A") (pinfunction "1A_1A") (pintype "passive"))
      (node (ref "JP3") (pin "1") (pinfunction "1_1") (pintype "passive"))
      (node (ref "R23") (pin "1") (pinfunction "1_1") (pintype "passive"))
    )
    (net (code "41") (name "Net-(J5-Pad1B)") (class "Default")
      (node (ref "J5") (pin "1B") (pinfunction "1B_1B") (pintype "passive"))
      (node (ref "JP9") (pin "1") (pinfunction "1_1") (pintype "passive"))
      (node (ref "R29") (pin "1") (pinfunction "1_1") (pintype "passive"))
    )
    (net (code "42") (name "Net-(J5-Pad2A)") (class "Default")
      (node (ref "J5") (pin "2A") (pinfunction "2A_2A") (pintype "passive"))
      (node (ref "JP6") (pin "1") (pinfunction "1_1") (pintype "passive"))
      (node (ref "R26") (pin "2") (pinfunction "2_2") (pintype "passive"))
    )
    (net (code "43") (name "Net-(J5-Pad2B)") (class "Default")
      (node (ref "J5") (pin "2B") (pinfunction "2B_2B") (pintype "passive"))
      (node (ref "JP12") (pin "1") (pinfunction "1_1") (pintype "passive"))
      (node (ref "R32") (pin "2") (pinfunction "2_2") (pintype "passive"))
    )
    (net (code "44") (name "Net-(JP1-Pad2)") (class "Default")
      (node (ref "JP1") (pin "2") (pinfunction "2_2") (pintype "passive"))
      (node (ref "R2") (pin "1") (pinfunction "1_1") (pintype "passive"))
      (node (ref "R21") (pin "2") (pinfunction "2_2") (pintype "passive"))
    )
    (net (code "45") (name "Net-(JP2-Pad2)") (class "Default")
      (node (ref "JP2") (pin "2") (pinfunction "2_2") (pintype "passive"))
      (node (ref "R1") (pin "1") (pinfunction "1_1") (pintype "passive"))
      (node (ref "R22") (pin "2") (pinfunction "2_2") (pintype "passive"))
    )
    (net (code "46") (name "Net-(JP3-Pad2)") (class "Default")
      (node (ref "JP3") (pin "2") (pinfunction "2_2") (pintype "passive"))
      (node (ref "R23") (pin "2") (pinfunction "2_2") (pintype "passive"))
      (node (ref "R3") (pin "1") (pinfunction "1_1") (pintype "passive"))
    )
    (net (code "47") (name "Net-(JP4-Pad2)") (class "Default")
      (node (ref "JP4") (pin "2") (pinfunction "2_2") (pintype "passive"))
      (node (ref "R24") (pin "1") (pinfunction "1_1") (pintype "passive"))
      (node (ref "R5") (pin "1") (pinfunction "1_1") (pintype "passive"))
    )
    (net (code "48") (name "Net-(JP5-Pad2)") (class "Default")
      (node (ref "JP5") (pin "2") (pinfunction "2_2") (pintype "passive"))
      (node (ref "R25") (pin "1") (pinfunction "1_1") (pintype "passive"))
      (node (ref "R4") (pin "1") (pinfunction "1_1") (pintype "passive"))
    )
    (net (code "49") (name "Net-(JP6-Pad2)") (class "Default")
      (node (ref "JP6") (pin "2") (pinfunction "2_2") (pintype "passive"))
      (node (ref "R26") (pin "1") (pinfunction "1_1") (pintype "passive"))
      (node (ref "R6") (pin "1") (pinfunction "1_1") (pintype "passive"))
    )
    (net (code "50") (name "Net-(JP7-Pad2)") (class "Default")
      (node (ref "JP7") (pin "2") (pinfunction "2_2") (pintype "passive"))
      (node (ref "R27") (pin "2") (pinfunction "2_2") (pintype "passive"))
      (node (ref "R7") (pin "1") (pinfunction "1_1") (pintype "passive"))
    )
    (net (code "51") (name "Net-(JP8-Pad2)") (class "Default")
      (node (ref "JP8") (pin "2") (pinfunction "2_2") (pintype "passive"))
      (node (ref "R28") (pin "2") (pinfunction "2_2") (pintype "passive"))
      (node (ref "R8") (pin "1") (pinfunction "1_1") (pintype "passive"))
    )
    (net (code "52") (name "Net-(JP9-Pad2)") (class "Default")
      (node (ref "JP9") (pin "2") (pinfunction "2_2") (pintype "passive"))
      (node (ref "R29") (pin "2") (pinfunction "2_2") (pintype "passive"))
      (node (ref "R9") (pin "1") (pinfunction "1_1") (pintype "passive"))
    )
    (net (code "53") (name "Net-(JP10-Pad2)") (class "Default")
      (node (ref "JP10") (pin "2") (pinfunction "2_2") (pintype "passive"))
      (node (ref "R10") (pin "1") (pinfunction "1_1") (pintype "passive"))
      (node (ref "R30") (pin "1") (pinfunction "1_1") (pintype "passive"))
    )
    (net (code "54") (name "Net-(JP11-Pad2)") (class "Default")
      (node (ref "JP11") (pin "2") (pinfunction "2_2") (pintype "passive"))
      (node (ref "R11") (pin "1") (pinfunction "1_1") (pintype "passive"))
      (node (ref "R31") (pin "1") (pinfunction "1_1") (pintype "passive"))
    )
    (net (code "55") (name "Net-(JP12-Pad2)") (class "Default")
      (node (ref "JP12") (pin "2") (pinfunction "2_2") (pintype "passive"))
      (node (ref "R12") (pin "1") (pinfunction "1_1") (pintype "passive"))
      (node (ref "R32") (pin "1") (pinfunction "1_1") (pintype "passive"))
    )
    (net (code "56") (name "Net-(JP13-Pad2)") (class "Default")
      (node (ref "JP13") (pin "2") (pinfunction "2_2") (pintype "passive"))
      (node (ref "R13") (pin "1") (pinfunction "1_1") (pintype "passive"))
      (node (ref "R33") (pin "2") (pinfunction "2_2") (pintype "passive"))
    )
    (net (code "57") (name "Net-(JP14-Pad2)") (class "Default")
      (node (ref "JP14") (pin "2") (pinfunction "2_2") (pintype "passive"))
      (node (ref "R14") (pin "1") (pinfunction "1_1") (pintype "passive"))
      (node (ref "R34") (pin "2") (pinfunction "2_2") (pintype "passive"))
    )
    (net (code "58") (name "Net-(JP15-Pad2)") (class "Default")
      (node (ref "JP15") (pin "2") (pinfunction "2_2") (pintype "passive"))
      (node (ref "R15") (pin "1") (pinfunction "1_1") (pintype "passive"))
      (node (ref "R35") (pin "1") (pinfunction "1_1") (pintype "passive"))
    )
    (net (code "59") (name "Net-(JP16-Pad2)") (class "Default")
      (node (ref "JP16") (pin "2") (pinfunction "2_2") (pintype "passive"))
      (node (ref "R16") (pin "1") (pinfunction "1_1") (pintype "passive"))
      (node (ref "R36") (pin "1") (pinfunction "1_1") (pintype "passive"))
    )
    (net (code "60") (name "Net-(JP17-Pad2)") (class "Default")
      (node (ref "JP17") (pin "2") (pinfunction "2_2") (pintype "passive"))
      (node (ref "R17") (pin "1") (pinfunction "1_1") (pintype "passive"))
      (node (ref "R37") (pin "2") (pinfunction "2_2") (pintype "passive"))
    )
    (net (code "61") (name "Net-(JP18-Pad2)") (class "Default")
      (node (ref "JP18") (pin "2") (pinfunction "2_2") (pintype "passive"))
      (node (ref "R18") (pin "1") (pinfunction "1_1") (pintype "passive"))
      (node (ref "R38") (pin "2") (pinfunction "2_2") (pintype "passive"))
    )
    (net (code "62") (name "Net-(JP19-Pad2)") (class "Default")
      (node (ref "JP19") (pin "2") (pinfunction "2_2") (pintype "passive"))
      (node (ref "R19") (pin "1") (pinfunction "1_1") (pintype "passive"))
      (node (ref "R39") (pin "1") (pinfunction "1_1") (pintype "passive"))
    )
    (net (code "63") (name "Net-(JP20-Pad2)") (class "Default")
      (node (ref "JP20") (pin "2") (pinfunction "2_2") (pintype "passive"))
      (node (ref "R20") (pin "1") (pinfunction "1_1") (pintype "passive"))
      (node (ref "R40") (pin "1") (pinfunction "1_1") (pintype "passive"))
    )
    (net (code "64") (name "unconnected-(J1-Pad4A)") (class "Default")
      (node (ref "J1") (pin "4A") (pinfunction "4A_4A") (pintype "passive+no_connect"))
    )
    (net (code "65") (name "unconnected-(J1-Pad4B)") (class "Default")
      (node (ref "J1") (pin "4B") (pinfunction "4B_4B") (pintype "passive+no_connect"))
    )
    (net (code "66") (name "unconnected-(J1-Pad5A)") (class "Default")
      (node (ref "J1") (pin "5A") (pinfunction "5A_5A") (pintype "passive+no_connect"))
    )
    (net (code "67") (name "unconnected-(J1-Pad5B)") (class "Default")
      (node (ref "J1") (pin "5B") (pinfunction "5B_5B") (pintype "passive+no_connect"))
    )
    (net (code "68") (name "unconnected-(J1-Pad7A)") (class "Default")
      (node (ref "J1") (pin "7A") (pinfunction "7A_7A") (pintype "passive+no_connect"))
    )
    (net (code "69") (name "unconnected-(J1-Pad7B)") (class "Default")
      (node (ref "J1") (pin "7B") (pinfunction "7B_7B") (pintype "passive+no_connect"))
    )
    (net (code "70") (name "unconnected-(J1-Pad8A)") (class "Default")
      (node (ref "J1") (pin "8A") (pinfunction "8A_8A") (pintype "passive+no_connect"))
    )
    (net (code "71") (name "unconnected-(J1-Pad8B)") (class "Default")
      (node (ref "J1") (pin "8B") (pinfunction "8B_8B") (pintype "passive+no_connect"))
    )
    (net (code "72") (name "unconnected-(J2-Pad4A)") (class "Default")
      (node (ref "J2") (pin "4A") (pinfunction "4A_4A") (pintype "passive+no_connect"))
    )
    (net (code "73") (name "unconnected-(J2-Pad4B)") (class "Default")
      (node (ref "J2") (pin "4B") (pinfunction "4B_4B") (pintype "passive+no_connect"))
    )
    (net (code "74") (name "unconnected-(J2-Pad5A)") (class "Default")
      (node (ref "J2") (pin "5A") (pinfunction "5A_5A") (pintype "passive+no_connect"))
    )
    (net (code "75") (name "unconnected-(J2-Pad5B)") (class "Default")
      (node (ref "J2") (pin "5B") (pinfunction "5B_5B") (pintype "passive+no_connect"))
    )
    (net (code "76") (name "unconnected-(J2-Pad7A)") (class "Default")
      (node (ref "J2") (pin "7A") (pinfunction "7A_7A") (pintype "passive+no_connect"))
    )
    (net (code "77") (name "unconnected-(J2-Pad7B)") (class "Default")
      (node (ref "J2") (pin "7B") (pinfunction "7B_7B") (pintype "passive+no_connect"))
    )
    (net (code "78") (name "unconnected-(J2-Pad8A)") (class "Default")
      (node (ref "J2") (pin "8A") (pinfunction "8A_8A") (pintype "passive+no_connect"))
    )
    (net (code "79") (name "unconnected-(J2-Pad8B)") (class "Default")
      (node (ref "J2") (pin "8B") (pinfunction "8B_8B") (pintype "passive+no_connect"))
    )
    (net (code "80") (name "unconnected-(J3-Pad4A)") (class "Default")
      (node (ref "J3") (pin "4A") (pinfunction "4A_4A") (pintype "passive+no_connect"))
    )
    (net (code "81") (name "unconnected-(J3-Pad4B)") (class "Default")
      (node (ref "J3") (pin "4B") (pinfunction "4B_4B") (pintype "passive+no_connect"))
    )
    (net (code "82") (name "unconnected-(J3-Pad5A)") (class "Default")
      (node (ref "J3") (pin "5A") (pinfunction "5A_5A") (pintype "passive+no_connect"))
    )
    (net (code "83") (name "unconnected-(J3-Pad5B)") (class "Default")
      (node (ref "J3") (pin "5B") (pinfunction "5B_5B") (pintype "passive+no_connect"))
    )
    (net (code "84") (name "unconnected-(J3-Pad7A)") (class "Default")
      (node (ref "J3") (pin "7A") (pinfunction "7A_7A") (pintype "passive+no_connect"))
    )
    (net (code "85") (name "unconnected-(J3-Pad7B)") (class "Default")
      (node (ref "J3") (pin "7B") (pinfunction "7B_7B") (pintype "passive+no_connect"))
    )
    (net (code "86") (name "unconnected-(J3-Pad8A)") (class "Default")
      (node (ref "J3") (pin "8A") (pinfunction "8A_8A") (pintype "passive+no_connect"))
    )
    (net (code "87") (name "unconnected-(J3-Pad8B)") (class "Default")
      (node (ref "J3") (pin "8B") (pinfunction "8B_8B") (pintype "passive+no_connect"))
    )
    (net (code "88") (name "unconnected-(J4-Pad4A)") (class "Default")
      (node (ref "J4") (pin "4A") (pinfunction "4A_4A") (pintype "passive+no_connect"))
    )
    (net (code "89") (name "unconnected-(J4-Pad4B)") (class "Default")
      (node (ref "J4") (pin "4B") (pinfunction "4B_4B") (pintype "passive+no_connect"))
    )
    (net (code "90") (name "unconnected-(J4-Pad5A)") (class "Default")
      (node (ref "J4") (pin "5A") (pinfunction "5A_5A") (pintype "passive+no_connect"))
    )
    (net (code "91") (name "unconnected-(J4-Pad5B)") (class "Default")
      (node (ref "J4") (pin "5B") (pinfunction "5B_5B") (pintype "passive+no_connect"))
    )
    (net (code "92") (name "unconnected-(J4-Pad7A)") (class "Default")
      (node (ref "J4") (pin "7A") (pinfunction "7A_7A") (pintype "passive+no_connect"))
    )
    (net (code "93") (name "unconnected-(J4-Pad7B)") (class "Default")
      (node (ref "J4") (pin "7B") (pinfunction "7B_7B") (pintype "passive+no_connect"))
    )
    (net (code "94") (name "unconnected-(J4-Pad8A)") (class "Default")
      (node (ref "J4") (pin "8A") (pinfunction "8A_8A") (pintype "passive+no_connect"))
    )
    (net (code "95") (name "unconnected-(J4-Pad8B)") (class "Default")
      (node (ref "J4") (pin "8B") (pinfunction "8B_8B") (pintype "passive+no_connect"))
    )
    (net (code "96") (name "unconnected-(J5-Pad4A)") (class "Default")
      (node (ref "J5") (pin "4A") (pinfunction "4A_4A") (pintype "passive+no_connect"))
    )
    (net (code "97") (name "unconnected-(J5-Pad4B)") (class "Default")
      (node (ref "J5") (pin "4B") (pinfunction "4B_4B") (pintype "passive+no_connect"))
    )
    (net (code "98") (name "unconnected-(J5-Pad5A)") (class "Default")
      (node (ref "J5") (pin "5A") (pinfunction "5A_5A") (pintype "passive+no_connect"))
    )
    (net (code "99") (name "unconnected-(J5-Pad5B)") (class "Default")
      (node (ref "J5") (pin "5B") (pinfunction "5B_5B") (pintype "passive+no_connect"))
    )
    (net (code "100") (name "unconnected-(J5-Pad7A)") (class "Default")
      (node (ref "J5") (pin "7A") (pinfunction "7A_7A") (pintype "passive+no_connect"))
    )
    (net (code "101") (name "unconnected-(J5-Pad7B)") (class "Default")
      (node (ref "J5") (pin "7B") (pinfunction "7B_7B") (pintype "passive+no_connect"))
    )
    (net (code "102") (name "unconnected-(J5-Pad8A)") (class "Default")
      (node (ref "J5") (pin "8A") (pinfunction "8A_8A") (pintype "passive+no_connect"))
    )
    (net (code "103") (name "unconnected-(J5-Pad8B)") (class "Default")
      (node (ref "J5") (pin "8B") (pinfunction "8B_8B") (pintype "passive+no_connect"))
    )
  )
)
